# SL_Config_2E.net
KiCad netlist of a schematic drawn in Altium Designer
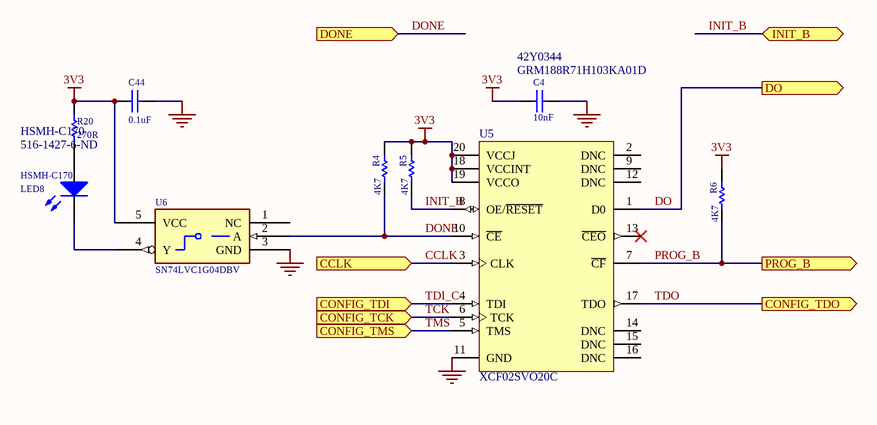
[diagram p0: SL_Config_2E.SchDoc]

(export (version "E")
  (design (tool "Eeschema 10.0.6"))
  (components
    (comp (ref "C4")
      (value "10nF")
      (footprint "CC1608-0603")
      (description "Capacitor")
      (fields
        (field (name "SUPPLIER PART NUMBER 1") "GRM188R71H103KA01D")
        (field (name "SUPPLIER PART NUMBER 2") "42Y0344")
      )
      (libsource (lib "SpiritLevel_2E") (part "CAP"))
    )
    (comp (ref "C44")
      (value "0.1uF")
      (footprint "CC2012-0805")
      (description "Capacitor")
      (libsource (lib "SpiritLevel_2E") (part "CAP"))
    )
    (comp (ref "LED8")
      (value "HSMH-C170")
      (footprint "Spirit_Level_Project:SMD _LED")
      (description "Typical RED GaAs SMD LED Agilent make")
      (fields
        (field (name "SUPPLIER PART NUMBER 1") "516-1427-6-ND")
        (field (name "SUPPLIER PART NUMBER 2") "HSMH-C170")
      )
      (libsource (lib "SpiritLevel_2E") (part "HSMX-C670"))
    )
    (comp (ref "R4")
      (value "4K7")
      (footprint "Spirit_Level_Project:CR2012-0805")
      (description "Resistor")
      (libsource (lib "SpiritLevel_2E") (part "RES"))
    )
    (comp (ref "R5")
      (value "4K7")
      (footprint "Spirit_Level_Project:CR2012-0805")
      (description "Resistor")
      (libsource (lib "SpiritLevel_2E") (part "RES"))
    )
    (comp (ref "R6")
      (value "4K7")
      (footprint "Spirit_Level_Project:CR2012-0805")
      (description "Resistor")
      (libsource (lib "SpiritLevel_2E") (part "RES"))
    )
    (comp (ref "R20")
      (value "270R")
      (footprint "Spirit_Level_Project:CR2012-0805")
      (description "Resistor")
      (libsource (lib "SpiritLevel_2E") (part "RES"))
    )
    (comp (ref "U5")
      (value "XCF02SVO20C")
      (footprint "Spirit_Level_Project:VO20")
      (libsource (lib "SpiritLevel_2E") (part "XCF02SVO20C"))
    )
    (comp (ref "U6")
      (value "SN74LVC1G04DBV")
      (footprint "Spirit_Level_Project:SO-G5/P.95")
      (fields (field (name "MANUFACTURER") "TI"))
      (libsource (lib "SpiritLevel_2E") (part "SN74AHC1G04DBVR"))
    )
  )
  (nets
    (net (code "1") (name "/CCLK") (class "Default")
      (node (ref "U5") (pin "3") (pinfunction "CLK_3") (pintype "input"))
    )
    (net (code "2") (name "/DO") (class "Default")
      (node (ref "U5") (pin "1") (pinfunction "D0_1") (pintype "tri_state"))
    )
    (net (code "3") (name "/DONE") (class "Default")
      (node (ref "R4") (pin "2") (pinfunction "2_2") (pintype "passive"))
      (node (ref "U5") (pin "10") (pinfunction "~{CE}_10") (pintype "input"))
      (node (ref "U6") (pin "2") (pinfunction "A_2") (pintype "input"))
    )
    (net (code "4") (name "/INIT_B") (class "Default")
      (node (ref "R5") (pin "2") (pinfunction "2_2") (pintype "passive"))
      (node (ref "U5") (pin "8") (pinfunction "OE/~{RESET}_8") (pintype "bidirectional"))
    )
    (net (code "5") (name "/PROG_B") (class "Default")
      (node (ref "R6") (pin "2") (pinfunction "2_2") (pintype "passive"))
      (node (ref "U5") (pin "7") (pinfunction "~{CF}_7") (pintype "open_collector"))
    )
    (net (code "6") (name "/TCK") (class "Default")
      (node (ref "U5") (pin "6") (pinfunction "TCK_6") (pintype "input"))
    )
    (net (code "7") (name "/TDI_C") (class "Default")
      (node (ref "U5") (pin "4") (pinfunction "TDI_4") (pintype "input"))
    )
    (net (code "8") (name "/TDO") (class "Default")
      (node (ref "U5") (pin "17") (pinfunction "TDO_17") (pintype "output"))
    )
    (net (code "9") (name "/TMS") (class "Default")
      (node (ref "U5") (pin "5") (pinfunction "TMS_5") (pintype "input"))
    )
    (net (code "10") (name "3V3") (class "Default")
      (node (ref "C4") (pin "1") (pinfunction "1_1") (pintype "passive"))
      (node (ref "C44") (pin "2") (pinfunction "2_2") (pintype "passive"))
      (node (ref "R20") (pin "2") (pinfunction "2_2") (pintype "passive"))
      (node (ref "R4") (pin "1") (pinfunction "1_1") (pintype "passive"))
      (node (ref "R5") (pin "1") (pinfunction "1_1") (pintype "passive"))
      (node (ref "R6") (pin "1") (pinfunction "1_1") (pintype "passive"))
      (node (ref "U5") (pin "18") (pinfunction "VCCINT_18") (pintype "power_in"))
      (node (ref "U5") (pin "19") (pinfunction "VCCO_19") (pintype "power_in"))
      (node (ref "U5") (pin "20") (pinfunction "VCCJ_20") (pintype "power_in"))
      (node (ref "U6") (pin "5") (pinfunction "VCC_5") (pintype "power_in"))
    )
    (net (code "11") (name "GND") (class "Default")
      (node (ref "C4") (pin "2") (pinfunction "2_2") (pintype "passive"))
      (node (ref "C44") (pin "1") (pinfunction "1_1") (pintype "passive"))
      (node (ref "U5") (pin "11") (pinfunction "GND_11") (pintype "power_in"))
      (node (ref "U6") (pin "3") (pinfunction "GND_3") (pintype "power_in"))
    )
    (net (code "12") (name "Net-(LED8-A)") (class "Default")
      (node (ref "LED8") (pin "1") (pinfunction "A_1") (pintype "passive"))
      (node (ref "R20") (pin "1") (pinfunction "1_1") (pintype "passive"))
    )
    (net (code "13") (name "Net-(LED8-K)") (class "Default")
      (node (ref "LED8") (pin "2") (pinfunction "K_2") (pintype "passive"))
      (node (ref "U6") (pin "4") (pinfunction "Y_4") (pintype "output"))
    )
    (net (code "14") (name "unconnected-(U5-DNC-Pad2)") (class "Default")
      (node (ref "U5") (pin "2") (pinfunction "DNC_2") (pintype "passive"))
    )
    (net (code "15") (name "unconnected-(U5-DNC-Pad9)") (class "Default")
      (node (ref "U5") (pin "9") (pinfunction "DNC_9") (pintype "passive"))
    )
    (net (code "16") (name "unconnected-(U5-DNC-Pad12)") (class "Default")
      (node (ref "U5") (pin "12") (pinfunction "DNC_12") (pintype "passive"))
    )
    (net (code "17") (name "unconnected-(U5-DNC-Pad14)") (class "Default")
      (node (ref "U5") (pin "14") (pinfunction "DNC_14") (pintype "passive"))
    )
    (net (code "18") (name "unconnected-(U5-DNC-Pad15)") (class "Default")
      (node (ref "U5") (pin "15") (pinfunction "DNC_15") (pintype "passive"))
    )
    (net (code "19") (name "unconnected-(U5-DNC-Pad16)") (class "Default")
      (node (ref "U5") (pin "16") (pinfunction "DNC_16") (pintype "passive"))
    )
    (net (code "20") (name "unconnected-(U5-~{CEO}-Pad13)") (class "Default")
      (node (ref "U5") (pin "13") (pinfunction "~{CEO}_13") (pintype "output+no_connect"))
    )
    (net (code "21") (name "unconnected-(U6-NC-Pad1)") (class "Default")
      (node (ref "U6") (pin "1") (pinfunction "NC_1") (pintype "passive"))
    )
  )
)
